# new_power.net
KiCad netlist of a schematic drawn in EAGLE
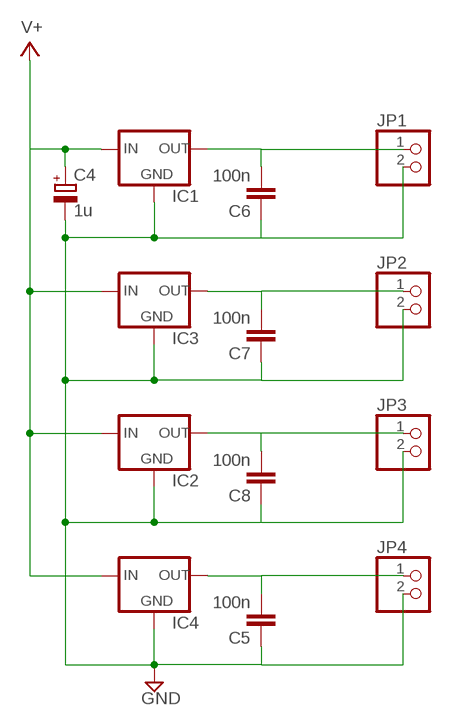
[diagram p0: schematic, sheet 1]

(export (version "E")
  (design (tool "Eeschema 10.0.6"))
  (components
    (comp (ref "C4")
      (value "1u")
      (footprint "eagle-import:E2-4")
      (libsource (lib "eagle-import") (part "CPOL-EUE2-4"))
    )
    (comp (ref "C5")
      (value "100n")
      (footprint "eagle-import:C025-024X044")
      (libsource (lib "eagle-import") (part "C-EU025-024X044"))
    )
    (comp (ref "C6")
      (value "100n")
      (footprint "eagle-import:C025-024X044")
      (libsource (lib "eagle-import") (part "C-EU025-024X044"))
    )
    (comp (ref "C7")
      (value "100n")
      (footprint "eagle-import:C025-024X044")
      (libsource (lib "eagle-import") (part "C-EU025-024X044"))
    )
    (comp (ref "C8")
      (value "100n")
      (footprint "eagle-import:C025-024X044")
      (libsource (lib "eagle-import") (part "C-EU025-024X044"))
    )
    (comp (ref "IC1")
      (value "78XX-TO3")
      (footprint "eagle-import:TO3-78")
      (libsource (lib "eagle-import") (part "78XX-TO3"))
    )
    (comp (ref "IC2")
      (value "78XX-TO3")
      (footprint "eagle-import:TO3-78")
      (libsource (lib "eagle-import") (part "78XX-TO3"))
    )
    (comp (ref "IC3")
      (value "78XX-TO3")
      (footprint "eagle-import:TO3-78")
      (libsource (lib "eagle-import") (part "78XX-TO3"))
    )
    (comp (ref "IC4")
      (value "78XX-TO3")
      (footprint "eagle-import:TO3-78")
      (libsource (lib "eagle-import") (part "78XX-TO3"))
    )
    (comp (ref "JP1")
      (value "PINHD-1X2")
      (footprint "eagle-import:1X02")
      (libsource (lib "eagle-import") (part "PINHD-1X2"))
    )
    (comp (ref "JP2")
      (value "PINHD-1X2")
      (footprint "eagle-import:1X02")
      (libsource (lib "eagle-import") (part "PINHD-1X2"))
    )
    (comp (ref "JP3")
      (value "PINHD-1X2")
      (footprint "eagle-import:1X02")
      (libsource (lib "eagle-import") (part "PINHD-1X2"))
    )
    (comp (ref "JP4")
      (value "PINHD-1X2")
      (footprint "eagle-import:1X02")
      (libsource (lib "eagle-import") (part "PINHD-1X2"))
    )
  )
  (nets
    (net (code "1") (name "GND") (class "Default")
      (node (ref "C4") (pin "-") (pinfunction "-_-") (pintype "passive"))
      (node (ref "C5") (pin "1") (pinfunction "1_1") (pintype "passive"))
      (node (ref "C6") (pin "1") (pinfunction "1_1") (pintype "passive"))
      (node (ref "C7") (pin "1") (pinfunction "1_1") (pintype "passive"))
      (node (ref "C8") (pin "1") (pinfunction "1_1") (pintype "passive"))
      (node (ref "IC1") (pin "3") (pinfunction "GND_3") (pintype "input"))
      (node (ref "IC2") (pin "3") (pinfunction "GND_3") (pintype "input"))
      (node (ref "IC3") (pin "3") (pinfunction "GND_3") (pintype "input"))
      (node (ref "IC4") (pin "3") (pinfunction "GND_3") (pintype "input"))
      (node (ref "JP1") (pin "2") (pinfunction "2_2") (pintype "passive"))
      (node (ref "JP2") (pin "2") (pinfunction "2_2") (pintype "passive"))
      (node (ref "JP3") (pin "2") (pinfunction "2_2") (pintype "passive"))
      (node (ref "JP4") (pin "2") (pinfunction "2_2") (pintype "passive"))
    )
    (net (code "2") (name "Net-(IC1-OUT)") (class "Default")
      (node (ref "C6") (pin "2") (pinfunction "2_2") (pintype "passive"))
      (node (ref "IC1") (pin "1") (pinfunction "OUT_1") (pintype "passive"))
      (node (ref "JP1") (pin "1") (pinfunction "1_1") (pintype "passive"))
    )
    (net (code "3") (name "Net-(IC2-OUT)") (class "Default")
      (node (ref "C8") (pin "2") (pinfunction "2_2") (pintype "passive"))
      (node (ref "IC2") (pin "1") (pinfunction "OUT_1") (pintype "passive"))
      (node (ref "JP3") (pin "1") (pinfunction "1_1") (pintype "passive"))
    )
    (net (code "4") (name "Net-(IC3-OUT)") (class "Default")
      (node (ref "C7") (pin "2") (pinfunction "2_2") (pintype "passive"))
      (node (ref "IC3") (pin "1") (pinfunction "OUT_1") (pintype "passive"))
      (node (ref "JP2") (pin "1") (pinfunction "1_1") (pintype "passive"))
    )
    (net (code "5") (name "Net-(IC4-OUT)") (class "Default")
      (node (ref "C5") (pin "2") (pinfunction "2_2") (pintype "passive"))
      (node (ref "IC4") (pin "1") (pinfunction "OUT_1") (pintype "passive"))
      (node (ref "JP4") (pin "1") (pinfunction "1_1") (pintype "passive"))
    )
    (net (code "6") (name "V+") (class "Default")
      (node (ref "C4") (pin "+") (pinfunction "+_+") (pintype "passive"))
      (node (ref "IC1") (pin "2") (pinfunction "IN_2") (pintype "input"))
      (node (ref "IC2") (pin "2") (pinfunction "IN_2") (pintype "input"))
      (node (ref "IC3") (pin "2") (pinfunction "IN_2") (pintype "input"))
      (node (ref "IC4") (pin "2") (pinfunction "IN_2") (pintype "input"))
    )
  )
)
